# Connectors.net
KiCad netlist of a schematic drawn in Altium Designer
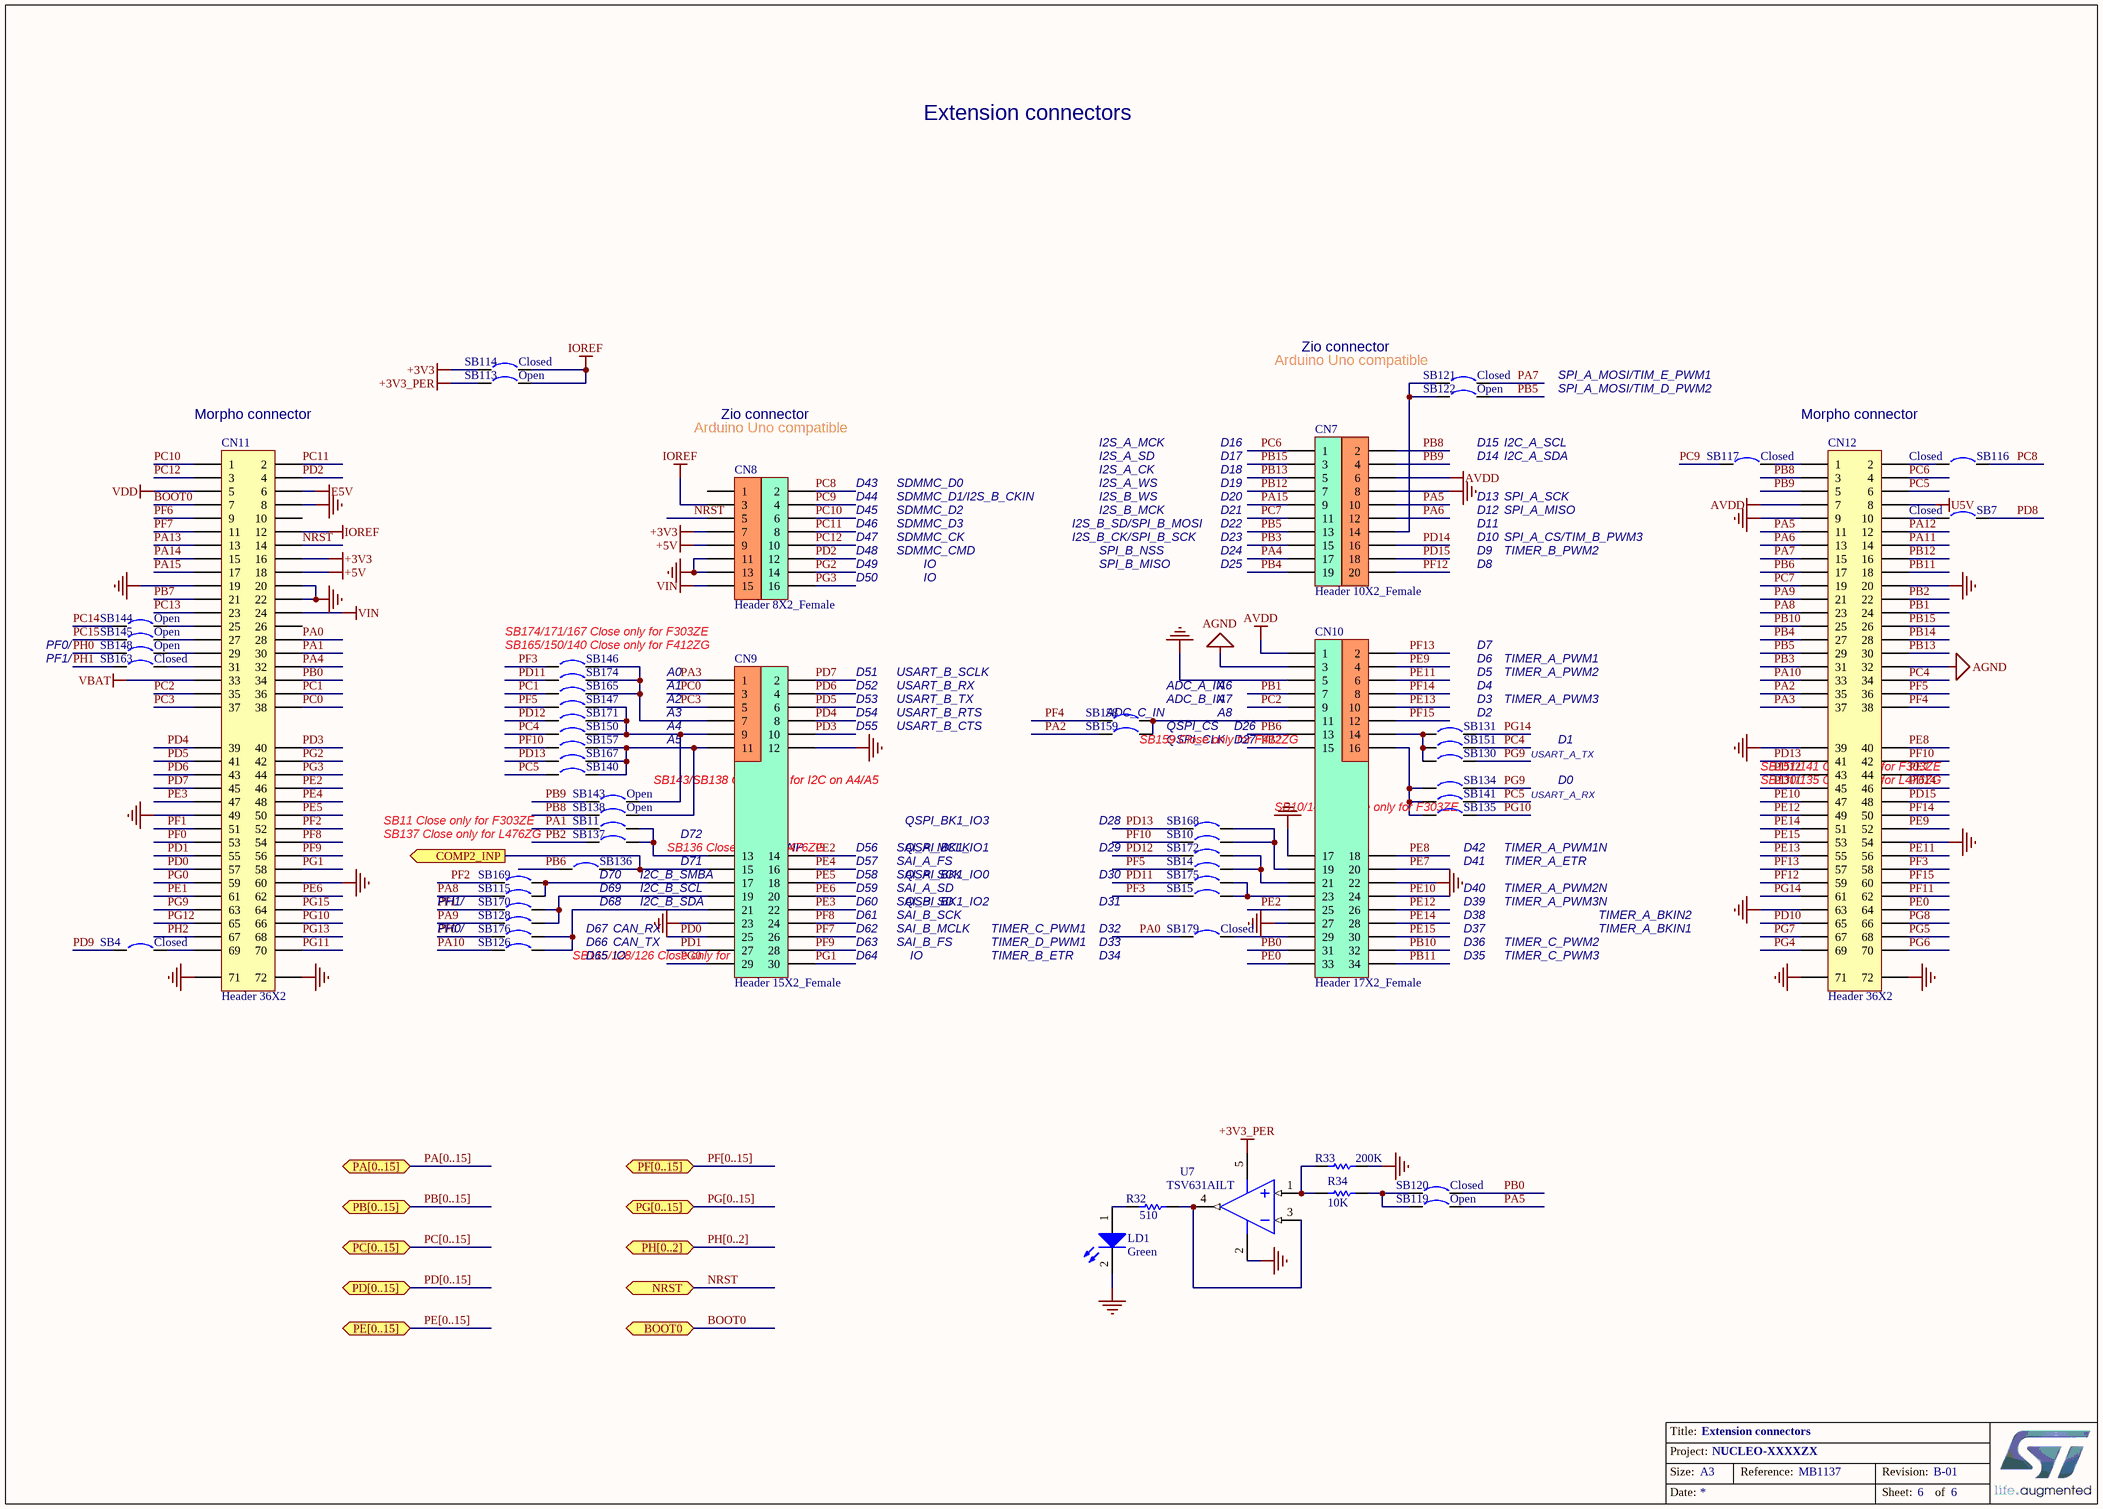
[diagram p0: Connectors.SchDoc]

(export (version "E")
  (design (tool "Eeschema 10.0.6"))
  (components
    (comp (ref "CN7")
      (value "Header 10X2_Female")
      (footprint "HDR_10x2_2R54_V_F")
      (description "Header, 10-Pin, Dual row,female")
      (fields (field (name "PUBLISHER") "Altium Limited"))
      (libsource (lib "MB1137") (part "Header 10X2_Female"))
    )
    (comp (ref "CN8")
      (value "Header 8X2_Female")
      (footprint "HDR_8x2_2R54_V_F")
      (description "Header, 8-Pin, Dual row,female")
      (fields (field (name "PUBLISHER") "Altium Limited"))
      (libsource (lib "MB1137") (part "Header 8X2_Female"))
    )
    (comp (ref "CN9")
      (value "Header 15X2_Female")
      (footprint "HDR_15x2_2R54_V_F")
      (description "Header, 15-Pin, Dual row,female")
      (fields (field (name "PUBLISHER") "Altium Limited"))
      (libsource (lib "MB1137") (part "Header 15X2_Female"))
    )
    (comp (ref "CN10")
      (value "Header 17X2_Female")
      (footprint "HDR_17x2_2R54_V_F")
      (description "Header, 17-Pin, Dual row,female")
      (fields (field (name "PUBLISHER") "Altium Limited"))
      (libsource (lib "MB1137") (part "Header 17X2_Female"))
    )
    (comp (ref "CN11")
      (value "Header 36X2")
      (footprint "HDR_2x36_2R54_V_M")
      (description "Header, 36-Pin, Dual row")
      (fields (field (name "PUBLISHER") "Altium Limited"))
      (libsource (lib "MB1137") (part "Header 36X2"))
    )
    (comp (ref "CN12")
      (value "Header 36X2")
      (footprint "HDR_2x36_2R54_V_M")
      (description "Header, 36-Pin, Dual row")
      (fields (field (name "PUBLISHER") "Altium Limited"))
      (libsource (lib "MB1137") (part "Header 36X2"))
    )
    (comp (ref "LD1")
      (value "Green")
      (footprint "0603D-G")
      (description "Typical RED, GREEN, YELLOW, AMBER GaAs LED")
      (fields (field (name "PUBLISHER") "Altium Limited"))
      (libsource (lib "Miscellaneous Devices") (part "LED2"))
    )
    (comp (ref "R32")
      (value "510")
      (footprint "0603R")
      (description "Resistor")
      (fields (field (name "PUBLISHER") "Altium Limited"))
      (libsource (lib "Miscellaneous Devices") (part "Res1"))
    )
    (comp (ref "R33")
      (value "200K")
      (footprint "0603R")
      (description "Resistor")
      (fields (field (name "PUBLISHER") "Altium Limited"))
      (libsource (lib "Miscellaneous Devices") (part "res1"))
    )
    (comp (ref "R34")
      (value "10K")
      (footprint "0603R")
      (description "Resistor")
      (fields (field (name "PUBLISHER") "Altium Limited"))
      (libsource (lib "Miscellaneous Devices") (part "res1"))
    )
    (comp (ref "SB4")
      (value "Closed")
      (footprint "SB_0603")
      (description "Circuit Breaker")
      (fields (field (name "PUBLISHER") "Altium Limited"))
      (libsource (lib "MB1167") (part "Circuit Breaker_close"))
    )
    (comp (ref "SB7")
      (value "Closed")
      (footprint "SB_0603")
      (description "Circuit Breaker")
      (fields (field (name "PUBLISHER") "Altium Limited"))
      (libsource (lib "MB1167") (part "Circuit Breaker_close"))
    )
    (comp (ref "SB10")
      (value "Circuit Breaker")
      (footprint "SB_0603")
      (fields (field (name "PUBLISHER") "Altium Limited"))
      (libsource (lib "") (part "Circuit Breaker_1"))
    )
    (comp (ref "SB11")
      (value "Circuit Breaker")
      (footprint "SB_0603")
      (fields (field (name "PUBLISHER") "Altium Limited"))
      (libsource (lib "MCD_TOOLS") (part "Circuit Breaker"))
    )
    (comp (ref "SB14")
      (value "Circuit Breaker")
      (footprint "SB_0603")
      (fields (field (name "PUBLISHER") "Altium Limited"))
      (libsource (lib "") (part "Circuit Breaker_1"))
    )
    (comp (ref "SB15")
      (value "Circuit Breaker")
      (footprint "SB_0603")
      (fields (field (name "PUBLISHER") "Altium Limited"))
      (libsource (lib "") (part "Circuit Breaker_1"))
    )
    (comp (ref "SB113")
      (value "Open")
      (footprint "SB_0603")
      (description "Circuit Breaker")
      (fields (field (name "PUBLISHER") "Altium Limited"))
      (libsource (lib "") (part "Circuit Breaker_1"))
    )
    (comp (ref "SB114")
      (value "Closed")
      (footprint "SB_0603")
      (description "Circuit Breaker")
      (fields (field (name "PUBLISHER") "Altium Limited"))
      (libsource (lib "MB1167") (part "Circuit Breaker_close"))
    )
    (comp (ref "SB115")
      (value "Circuit Breaker")
      (footprint "SB_0603")
      (fields (field (name "PUBLISHER") "Altium Limited"))
      (libsource (lib "MCD_TOOLS") (part "Circuit Breaker"))
    )
    (comp (ref "SB116")
      (value "Closed")
      (footprint "SB_0603")
      (description "Circuit Breaker")
      (fields (field (name "PUBLISHER") "Altium Limited"))
      (libsource (lib "") (part "Circuit Breaker_close_1"))
    )
    (comp (ref "SB117")
      (value "Closed")
      (footprint "SB_0603")
      (description "Circuit Breaker")
      (fields (field (name "PUBLISHER") "Altium Limited"))
      (libsource (lib "MB1167") (part "Circuit Breaker_close"))
    )
    (comp (ref "SB119")
      (value "Open")
      (footprint "SB_0603")
      (description "Circuit Breaker")
      (fields (field (name "PUBLISHER") "Altium Limited"))
      (libsource (lib "") (part "Circuit Breaker_1"))
    )
    (comp (ref "SB120")
      (value "Closed")
      (footprint "SB_0603")
      (description "Circuit Breaker")
      (fields (field (name "PUBLISHER") "Altium Limited"))
      (libsource (lib "") (part "Circuit Breaker_close_1"))
    )
    (comp (ref "SB121")
      (value "Closed")
      (footprint "SB_0603")
      (description "Circuit Breaker")
      (fields (field (name "PUBLISHER") "Altium Limited"))
      (libsource (lib "MB1167") (part "Circuit Breaker_close"))
    )
    (comp (ref "SB122")
      (value "Open")
      (footprint "SB_0603")
      (description "Circuit Breaker")
      (fields (field (name "PUBLISHER") "Altium Limited"))
      (libsource (lib "") (part "Circuit Breaker_1"))
    )
    (comp (ref "SB126")
      (value "Circuit Breaker")
      (footprint "SB_0603")
      (fields (field (name "PUBLISHER") "Altium Limited"))
      (libsource (lib "MCD_TOOLS") (part "Circuit Breaker"))
    )
    (comp (ref "SB128")
      (value "Circuit Breaker")
      (footprint "SB_0603")
      (fields (field (name "PUBLISHER") "Altium Limited"))
      (libsource (lib "MCD_TOOLS") (part "Circuit Breaker"))
    )
    (comp (ref "SB130")
      (value "Circuit Breaker")
      (footprint "SB_0603")
      (fields (field (name "PUBLISHER") "Altium Limited"))
      (libsource (lib "MCD_TOOLS") (part "Circuit Breaker"))
    )
    (comp (ref "SB131")
      (value "Circuit Breaker")
      (footprint "SB_0603")
      (fields (field (name "PUBLISHER") "Altium Limited"))
      (libsource (lib "MCD_TOOLS") (part "Circuit Breaker"))
    )
    (comp (ref "SB134")
      (value "Circuit Breaker")
      (footprint "SB_0603")
      (fields (field (name "PUBLISHER") "Altium Limited"))
      (libsource (lib "MCD_TOOLS") (part "Circuit Breaker"))
    )
    (comp (ref "SB135")
      (value "Circuit Breaker")
      (footprint "SB_0603")
      (fields (field (name "PUBLISHER") "Altium Limited"))
      (libsource (lib "MCD_TOOLS") (part "Circuit Breaker"))
    )
    (comp (ref "SB136")
      (value "Circuit Breaker")
      (footprint "SB_0603")
      (fields (field (name "PUBLISHER") "Altium Limited"))
      (libsource (lib "MCD_TOOLS") (part "Circuit Breaker"))
    )
    (comp (ref "SB137")
      (value "Circuit Breaker")
      (footprint "SB_0603")
      (fields (field (name "PUBLISHER") "Altium Limited"))
      (libsource (lib "MCD_TOOLS") (part "Circuit Breaker"))
    )
    (comp (ref "SB138")
      (value "Open")
      (footprint "SB_0603")
      (description "Circuit Breaker")
      (fields (field (name "PUBLISHER") "Altium Limited"))
      (libsource (lib "MB1167") (part "Circuit Breaker"))
    )
    (comp (ref "SB140")
      (value "Circuit Breaker")
      (footprint "SB_0603")
      (fields (field (name "PUBLISHER") "Altium Limited"))
      (libsource (lib "MCD_TOOLS") (part "Circuit Breaker"))
    )
    (comp (ref "SB141")
      (value "Circuit Breaker")
      (footprint "SB_0603")
      (fields (field (name "PUBLISHER") "Altium Limited"))
      (libsource (lib "MCD_TOOLS") (part "Circuit Breaker"))
    )
    (comp (ref "SB143")
      (value "Open")
      (footprint "SB_0603")
      (description "Circuit Breaker")
      (fields (field (name "PUBLISHER") "Altium Limited"))
      (libsource (lib "MB1167") (part "Circuit Breaker"))
    )
    (comp (ref "SB144")
      (value "Open")
      (footprint "SB_0603")
      (description "Circuit Breaker")
      (fields (field (name "PUBLISHER") "Altium Limited"))
      (libsource (lib "") (part "Circuit Breaker_1"))
    )
    (comp (ref "SB145")
      (value "Open")
      (footprint "SB_0603")
      (description "Circuit Breaker")
      (fields (field (name "PUBLISHER") "Altium Limited"))
      (libsource (lib "") (part "Circuit Breaker_1"))
    )
    (comp (ref "SB146")
      (value "Circuit Breaker")
      (footprint "SB_0603")
      (fields (field (name "PUBLISHER") "Altium Limited"))
      (libsource (lib "MCD_TOOLS") (part "Circuit Breaker"))
    )
    (comp (ref "SB147")
      (value "Circuit Breaker")
      (footprint "SB_0603")
      (fields (field (name "PUBLISHER") "Altium Limited"))
      (libsource (lib "MCD_TOOLS") (part "Circuit Breaker"))
    )
    (comp (ref "SB148")
      (value "Open")
      (footprint "SB_0603")
      (description "Circuit Breaker")
      (fields (field (name "PUBLISHER") "Altium Limited"))
      (libsource (lib "") (part "Circuit Breaker_1"))
    )
    (comp (ref "SB150")
      (value "Circuit Breaker")
      (footprint "SB_0603")
      (fields (field (name "PUBLISHER") "Altium Limited"))
      (libsource (lib "MCD_TOOLS") (part "Circuit Breaker"))
    )
    (comp (ref "SB151")
      (value "Circuit Breaker")
      (footprint "SB_0603")
      (fields (field (name "PUBLISHER") "Altium Limited"))
      (libsource (lib "MCD_TOOLS") (part "Circuit Breaker"))
    )
    (comp (ref "SB157")
      (value "Circuit Breaker")
      (footprint "SB_0603")
      (fields (field (name "PUBLISHER") "Altium Limited"))
      (libsource (lib "MCD_TOOLS") (part "Circuit Breaker"))
    )
    (comp (ref "SB158")
      (value "Circuit Breaker")
      (footprint "SB_0603")
      (fields (field (name "PUBLISHER") "Altium Limited"))
      (libsource (lib "") (part "Circuit Breaker_1"))
    )
    (comp (ref "SB159")
      (value "Circuit Breaker")
      (footprint "SB_0603")
      (fields (field (name "PUBLISHER") "Altium Limited"))
      (libsource (lib "") (part "Circuit Breaker_1"))
    )
    (comp (ref "SB163")
      (value "Closed")
      (footprint "SB_0603")
      (description "Circuit Breaker")
      (fields (field (name "PUBLISHER") "Altium Limited"))
      (libsource (lib "MB1167") (part "Circuit Breaker_close"))
    )
    (comp (ref "SB165")
      (value "Circuit Breaker")
      (footprint "SB_0603")
      (fields (field (name "PUBLISHER") "Altium Limited"))
      (libsource (lib "MCD_TOOLS") (part "Circuit Breaker"))
    )
    (comp (ref "SB167")
      (value "Circuit Breaker")
      (footprint "SB_0603")
      (fields (field (name "PUBLISHER") "Altium Limited"))
      (libsource (lib "MCD_TOOLS") (part "Circuit Breaker"))
    )
    (comp (ref "SB168")
      (value "Circuit Breaker")
      (footprint "SB_0603")
      (fields (field (name "PUBLISHER") "Altium Limited"))
      (libsource (lib "") (part "Circuit Breaker_1"))
    )
    (comp (ref "SB169")
      (value "Circuit Breaker")
      (footprint "SB_0603")
      (fields (field (name "PUBLISHER") "Altium Limited"))
      (libsource (lib "MCD_TOOLS") (part "Circuit Breaker"))
    )
    (comp (ref "SB170")
      (value "Circuit Breaker")
      (footprint "SB_0603")
      (fields (field (name "PUBLISHER") "Altium Limited"))
      (libsource (lib "MCD_TOOLS") (part "Circuit Breaker"))
    )
    (comp (ref "SB171")
      (value "Circuit Breaker")
      (footprint "SB_0603")
      (fields (field (name "PUBLISHER") "Altium Limited"))
      (libsource (lib "MCD_TOOLS") (part "Circuit Breaker"))
    )
    (comp (ref "SB172")
      (value "Circuit Breaker")
      (footprint "SB_0603")
      (fields (field (name "PUBLISHER") "Altium Limited"))
      (libsource (lib "") (part "Circuit Breaker_1"))
    )
    (comp (ref "SB174")
      (value "Circuit Breaker")
      (footprint "SB_0603")
      (fields (field (name "PUBLISHER") "Altium Limited"))
      (libsource (lib "MCD_TOOLS") (part "Circuit Breaker"))
    )
    (comp (ref "SB175")
      (value "Circuit Breaker")
      (footprint "SB_0603")
      (fields (field (name "PUBLISHER") "Altium Limited"))
      (libsource (lib "") (part "Circuit Breaker_1"))
    )
    (comp (ref "SB176")
      (value "Circuit Breaker")
      (footprint "SB_0603")
      (fields (field (name "PUBLISHER") "Altium Limited"))
      (libsource (lib "MCD_TOOLS") (part "Circuit Breaker"))
    )
    (comp (ref "SB179")
      (value "Closed")
      (footprint "SB_0603")
      (description "Circuit Breaker")
      (fields (field (name "PUBLISHER") "Altium Limited"))
      (libsource (lib "MB1167") (part "Circuit Breaker_close"))
    )
    (comp (ref "U7")
      (value "TSV631AILT")
      (footprint "SOT-23-5L")
      (libsource (lib "MB988") (part "TSV631AILT"))
    )
  )
  (nets
    (net (code "1") (name "+3V3") (class "Default")
      (node (ref "CN11") (pin "16") (pinfunction "16_16") (pintype "passive"))
      (node (ref "CN8") (pin "7") (pinfunction "7_7") (pintype "passive"))
      (node (ref "SB114") (pin "1") (pinfunction "1_1") (pintype "passive"))
    )
    (net (code "2") (name "+3V3_PER") (class "Default")
      (node (ref "SB113") (pin "1") (pinfunction "1_1") (pintype "passive"))
      (node (ref "U7") (pin "5") (pinfunction "VCC_5") (pintype "power_in"))
    )
    (net (code "3") (name "+5V") (class "Default")
      (node (ref "CN11") (pin "18") (pinfunction "18_18") (pintype "passive"))
      (node (ref "CN8") (pin "9") (pinfunction "9_9") (pintype "passive"))
    )
    (net (code "4") (name "/BOOT0") (class "Default")
      (node (ref "CN11") (pin "7") (pinfunction "7_7") (pintype "passive"))
    )
    (net (code "5") (name "/COMP2_INP") (class "Default")
      (node (ref "CN9") (pin "15") (pinfunction "15_15") (pintype "passive"))
      (node (ref "SB136") (pin "1") (pinfunction "1_1") (pintype "passive"))
    )
    (net (code "6") (name "/NRST") (class "Default")
      (node (ref "CN11") (pin "14") (pinfunction "14_14") (pintype "passive"))
      (node (ref "CN8") (pin "5") (pinfunction "5_5") (pintype "passive"))
    )
    (net (code "7") (name "/PA0") (class "Default")
      (node (ref "CN11") (pin "28") (pinfunction "28_28") (pintype "passive"))
      (node (ref "SB179") (pin "1") (pinfunction "1_1") (pintype "passive"))
    )
    (net (code "8") (name "/PA1") (class "Default")
      (node (ref "CN11") (pin "30") (pinfunction "30_30") (pintype "passive"))
      (node (ref "SB11") (pin "2") (pinfunction "2_2") (pintype "passive"))
    )
    (net (code "9") (name "/PA2") (class "Default")
      (node (ref "CN12") (pin "35") (pinfunction "35_35") (pintype "passive"))
      (node (ref "SB159") (pin "1") (pinfunction "1_1") (pintype "passive"))
    )
    (net (code "10") (name "/PA3") (class "Default")
      (node (ref "CN12") (pin "37") (pinfunction "37_37") (pintype "passive"))
      (node (ref "CN9") (pin "1") (pinfunction "1_1") (pintype "passive"))
    )
    (net (code "11") (name "/PA4") (class "Default")
      (node (ref "CN11") (pin "32") (pinfunction "32_32") (pintype "passive"))
      (node (ref "CN7") (pin "17") (pinfunction "17_17") (pintype "passive"))
    )
    (net (code "12") (name "/PA5") (class "Default")
      (node (ref "CN12") (pin "11") (pinfunction "11_11") (pintype "passive"))
      (node (ref "CN7") (pin "10") (pinfunction "10_10") (pintype "passive"))
      (node (ref "SB119") (pin "2") (pinfunction "2_2") (pintype "passive"))
    )
    (net (code "13") (name "/PA6") (class "Default")
      (node (ref "CN12") (pin "13") (pinfunction "13_13") (pintype "passive"))
      (node (ref "CN7") (pin "12") (pinfunction "12_12") (pintype "passive"))
    )
    (net (code "14") (name "/PA7") (class "Default")
      (node (ref "CN12") (pin "15") (pinfunction "15_15") (pintype "passive"))
      (node (ref "SB121") (pin "2") (pinfunction "2_2") (pintype "passive"))
    )
    (net (code "15") (name "/PA8") (class "Default")
      (node (ref "CN12") (pin "23") (pinfunction "23_23") (pintype "passive"))
      (node (ref "SB115") (pin "2") (pinfunction "2_2") (pintype "passive"))
    )
    (net (code "16") (name "/PA9") (class "Default")
      (node (ref "CN12") (pin "21") (pinfunction "21_21") (pintype "passive"))
      (node (ref "SB128") (pin "2") (pinfunction "2_2") (pintype "passive"))
    )
    (net (code "17") (name "/PA10") (class "Default")
      (node (ref "CN12") (pin "33") (pinfunction "33_33") (pintype "passive"))
      (node (ref "SB126") (pin "2") (pinfunction "2_2") (pintype "passive"))
    )
    (net (code "18") (name "/PA11") (class "Default")
      (node (ref "CN12") (pin "14") (pinfunction "14_14") (pintype "passive"))
    )
    (net (code "19") (name "/PA12") (class "Default")
      (node (ref "CN12") (pin "12") (pinfunction "12_12") (pintype "passive"))
    )
    (net (code "20") (name "/PA13") (class "Default")
      (node (ref "CN11") (pin "13") (pinfunction "13_13") (pintype "passive"))
    )
    (net (code "21") (name "/PA14") (class "Default")
      (node (ref "CN11") (pin "15") (pinfunction "15_15") (pintype "passive"))
    )
    (net (code "22") (name "/PA15") (class "Default")
      (node (ref "CN11") (pin "17") (pinfunction "17_17") (pintype "passive"))
      (node (ref "CN7") (pin "9") (pinfunction "9_9") (pintype "passive"))
    )
    (net (code "24") (name "/PB0") (class "Default")
      (node (ref "CN10") (pin "31") (pinfunction "31_31") (pintype "passive"))
      (node (ref "CN11") (pin "34") (pinfunction "34_34") (pintype "passive"))
      (node (ref "SB120") (pin "1") (pinfunction "1_1") (pintype "passive"))
    )
    (net (code "25") (name "/PB1") (class "Default")
      (node (ref "CN10") (pin "7") (pinfunction "7_7") (pintype "passive"))
      (node (ref "CN12") (pin "24") (pinfunction "24_24") (pintype "passive"))
    )
    (net (code "26") (name "/PB2") (class "Default")
      (node (ref "CN10") (pin "15") (pinfunction "15_15") (pintype "passive"))
      (node (ref "CN12") (pin "22") (pinfunction "22_22") (pintype "passive"))
      (node (ref "SB137") (pin "2") (pinfunction "2_2") (pintype "passive"))
    )
    (net (code "27") (name "/PB3") (class "Default")
      (node (ref "CN12") (pin "31") (pinfunction "31_31") (pintype "passive"))
      (node (ref "CN7") (pin "15") (pinfunction "15_15") (pintype "passive"))
    )
    (net (code "28") (name "/PB4") (class "Default")
      (node (ref "CN12") (pin "27") (pinfunction "27_27") (pintype "passive"))
      (node (ref "CN7") (pin "19") (pinfunction "19_19") (pintype "passive"))
    )
    (net (code "29") (name "/PB5") (class "Default")
      (node (ref "CN12") (pin "29") (pinfunction "29_29") (pintype "passive"))
      (node (ref "CN7") (pin "13") (pinfunction "13_13") (pintype "passive"))
      (node (ref "SB122") (pin "2") (pinfunction "2_2") (pintype "passive"))
    )
    (net (code "30") (name "/PB6") (class "Default")
      (node (ref "CN10") (pin "13") (pinfunction "13_13") (pintype "passive"))
      (node (ref "CN12") (pin "17") (pinfunction "17_17") (pintype "passive"))
      (node (ref "SB136") (pin "2") (pinfunction "2_2") (pintype "passive"))
    )
    (net (code "31") (name "/PB7") (class "Default")
      (node (ref "CN11") (pin "21") (pinfunction "21_21") (pintype "passive"))
    )
    (net (code "32") (name "/PB8") (class "Default")
      (node (ref "CN12") (pin "3") (pinfunction "3_3") (pintype "passive"))
      (node (ref "CN7") (pin "2") (pinfunction "2_2") (pintype "passive"))
      (node (ref "SB138") (pin "2") (pinfunction "2_2") (pintype "passive"))
    )
    (net (code "33") (name "/PB9") (class "Default")
      (node (ref "CN12") (pin "5") (pinfunction "5_5") (pintype "passive"))
      (node (ref "CN7") (pin "4") (pinfunction "4_4") (pintype "passive"))
      (node (ref "SB143") (pin "2") (pinfunction "2_2") (pintype "passive"))
    )
    (net (code "34") (name "/PB10") (class "Default")
      (node (ref "CN10") (pin "32") (pinfunction "32_32") (pintype "passive"))
      (node (ref "CN12") (pin "25") (pinfunction "25_25") (pintype "passive"))
    )
    (net (code "35") (name "/PB11") (class "Default")
      (node (ref "CN10") (pin "34") (pinfunction "34_34") (pintype "passive"))
      (node (ref "CN12") (pin "18") (pinfunction "18_18") (pintype "passive"))
    )
    (net (code "36") (name "/PB12") (class "Default")
      (node (ref "CN12") (pin "16") (pinfunction "16_16") (pintype "passive"))
      (node (ref "CN7") (pin "7") (pinfunction "7_7") (pintype "passive"))
    )
    (net (code "37") (name "/PB13") (class "Default")
      (node (ref "CN12") (pin "30") (pinfunction "30_30") (pintype "passive"))
      (node (ref "CN7") (pin "5") (pinfunction "5_5") (pintype "passive"))
    )
    (net (code "38") (name "/PB14") (class "Default")
      (node (ref "CN12") (pin "28") (pinfunction "28_28") (pintype "passive"))
    )
    (net (code "39") (name "/PB15") (class "Default")
      (node (ref "CN12") (pin "26") (pinfunction "26_26") (pintype "passive"))
      (node (ref "CN7") (pin "3") (pinfunction "3_3") (pintype "passive"))
    )
    (net (code "41") (name "/PC0") (class "Default")
      (node (ref "CN11") (pin "38") (pinfunction "38_38") (pintype "passive"))
      (node (ref "CN9") (pin "3") (pinfunction "3_3") (pintype "passive"))
    )
    (net (code "42") (name "/PC1") (class "Default")
      (node (ref "CN11") (pin "36") (pinfunction "36_36") (pintype "passive"))
      (node (ref "SB165") (pin "2") (pinfunction "2_2") (pintype "passive"))
    )
    (net (code "43") (name "/PC2") (class "Default")
      (node (ref "CN10") (pin "9") (pinfunction "9_9") (pintype "passive"))
      (node (ref "CN11") (pin "35") (pinfunction "35_35") (pintype "passive"))
    )
    (net (code "44") (name "/PC3") (class "Default")
      (node (ref "CN11") (pin "37") (pinfunction "37_37") (pintype "passive"))
      (node (ref "CN9") (pin "5") (pinfunction "5_5") (pintype "passive"))
    )
    (net (code "45") (name "/PC4") (class "Default")
      (node (ref "CN12") (pin "34") (pinfunction "34_34") (pintype "passive"))
      (node (ref "SB150") (pin "2") (pinfunction "2_2") (pintype "passive"))
      (node (ref "SB151") (pin "1") (pinfunction "1_1") (pintype "passive"))
    )
    (net (code "46") (name "/PC5") (class "Default")
      (node (ref "CN12") (pin "6") (pinfunction "6_6") (pintype "passive"))
      (node (ref "SB140") (pin "2") (pinfunction "2_2") (pintype "passive"))
      (node (ref "SB141") (pin "1") (pinfunction "1_1") (pintype "passive"))
    )
    (net (code "47") (name "/PC6") (class "Default")
      (node (ref "CN12") (pin "4") (pinfunction "4_4") (pintype "passive"))
      (node (ref "CN7") (pin "1") (pinfunction "1_1") (pintype "passive"))
    )
    (net (code "48") (name "/PC7") (class "Default")
      (node (ref "CN12") (pin "19") (pinfunction "19_19") (pintype "passive"))
      (node (ref "CN7") (pin "11") (pinfunction "11_11") (pintype "passive"))
    )
    (net (code "49") (name "/PC8") (class "Default")
      (node (ref "CN8") (pin "2") (pinfunction "2_2") (pintype "passive"))
      (node (ref "SB116") (pin "1") (pinfunction "1_1") (pintype "passive"))
    )
    (net (code "50") (name "/PC9") (class "Default")
      (node (ref "CN8") (pin "4") (pinfunction "4_4") (pintype "passive"))
      (node (ref "SB117") (pin "1") (pinfunction "1_1") (pintype "passive"))
    )
    (net (code "51") (name "/PC10") (class "Default")
      (node (ref "CN11") (pin "1") (pinfunction "1_1") (pintype "passive"))
      (node (ref "CN8") (pin "6") (pinfunction "6_6") (pintype "passive"))
    )
    (net (code "52") (name "/PC11") (class "Default")
      (node (ref "CN11") (pin "2") (pinfunction "2_2") (pintype "passive"))
      (node (ref "CN8") (pin "8") (pinfunction "8_8") (pintype "passive"))
    )
    (net (code "53") (name "/PC12") (class "Default")
      (node (ref "CN11") (pin "3") (pinfunction "3_3") (pintype "passive"))
      (node (ref "CN8") (pin "10") (pinfunction "10_10") (pintype "passive"))
    )
    (net (code "54") (name "/PC13") (class "Default")
      (node (ref "CN11") (pin "23") (pinfunction "23_23") (pintype "passive"))
    )
    (net (code "55") (name "/PC14") (class "Default")
      (node (ref "SB144") (pin "1") (pinfunction "1_1") (pintype "passive"))
    )
    (net (code "56") (name "/PC15") (class "Default")
      (node (ref "SB145") (pin "1") (pinfunction "1_1") (pintype "passive"))
    )
    (net (code "58") (name "/PD0") (class "Default")
      (node (ref "CN11") (pin "57") (pinfunction "57_57") (pintype "passive"))
      (node (ref "CN9") (pin "25") (pinfunction "25_25") (pintype "passive"))
    )
    (net (code "59") (name "/PD1") (class "Default")
      (node (ref "CN11") (pin "55") (pinfunction "55_55") (pintype "passive"))
      (node (ref "CN9") (pin "27") (pinfunction "27_27") (pintype "passive"))
    )
    (net (code "60") (name "/PD2") (class "Default")
      (node (ref "CN11") (pin "4") (pinfunction "4_4") (pintype "passive"))
      (node (ref "CN8") (pin "12") (pinfunction "12_12") (pintype "passive"))
    )
    (net (code "61") (name "/PD3") (class "Default")
      (node (ref "CN11") (pin "40") (pinfunction "40_40") (pintype "passive"))
      (node (ref "CN9") (pin "10") (pinfunction "10_10") (pintype "passive"))
    )
    (net (code "62") (name "/PD4") (class "Default")
      (node (ref "CN11") (pin "39") (pinfunction "39_39") (pintype "passive"))
      (node (ref "CN9") (pin "8") (pinfunction "8_8") (pintype "passive"))
    )
    (net (code "63") (name "/PD5") (class "Default")
      (node (ref "CN11") (pin "41") (pinfunction "41_41") (pintype "passive"))
      (node (ref "CN9") (pin "6") (pinfunction "6_6") (pintype "passive"))
    )
    (net (code "64") (name "/PD6") (class "Default")
      (node (ref "CN11") (pin "43") (pinfunction "43_43") (pintype "passive"))
      (node (ref "CN9") (pin "4") (pinfunction "4_4") (pintype "passive"))
    )
    (net (code "65") (name "/PD7") (class "Default")
      (node (ref "CN11") (pin "45") (pinfunction "45_45") (pintype "passive"))
      (node (ref "CN9") (pin "2") (pinfunction "2_2") (pintype "passive"))
    )
    (net (code "66") (name "/PD8") (class "Default")
      (node (ref "SB7") (pin "2") (pinfunction "2_2") (pintype "passive"))
    )
    (net (code "67") (name "/PD9") (class "Default")
      (node (ref "SB4") (pin "1") (pinfunction "1_1") (pintype "passive"))
    )
    (net (code "68") (name "/PD10") (class "Default")
      (node (ref "CN12") (pin "65") (pinfunction "65_65") (pintype "passive"))
    )
    (net (code "69") (name "/PD11") (class "Default")
      (node (ref "CN12") (pin "45") (pinfunction "45_45") (pintype "passive"))
      (node (ref "SB174") (pin "2") (pinfunction "2_2") (pintype "passive"))
      (node (ref "SB175") (pin "1") (pinfunction "1_1") (pintype "passive"))
    )
    (net (code "70") (name "/PD12") (class "Default")
      (node (ref "CN12") (pin "43") (pinfunction "43_43") (pintype "passive"))
      (node (ref "SB171") (pin "2") (pinfunction "2_2") (pintype "passive"))
      (node (ref "SB172") (pin "1") (pinfunction "1_1") (pintype "passive"))
    )
    (net (code "71") (name "/PD13") (class "Default")
      (node (ref "CN12") (pin "41") (pinfunction "41_41") (pintype "passive"))
      (node (ref "SB167") (pin "2") (pinfunction "2_2") (pintype "passive"))
      (node (ref "SB168") (pin "1") (pinfunction "1_1") (pintype "passive"))
    )
    (net (code "72") (name "/PD14") (class "Default")
      (node (ref "CN12") (pin "46") (pinfunction "46_46") (pintype "passive"))
      (node (ref "CN7") (pin "16") (pinfunction "16_16") (pintype "passive"))
    )
    (net (code "73") (name "/PD15") (class "Default")
      (node (ref "CN12") (pin "48") (pinfunction "48_48") (pintype "passive"))
      (node (ref "CN7") (pin "18") (pinfunction "18_18") (pintype "passive"))
    )
    (net (code "75") (name "/PE0") (class "Default")
      (node (ref "CN10") (pin "33") (pinfunction "33_33") (pintype "passive"))
      (node (ref "CN12") (pin "64") (pinfunction "64_64") (pintype "passive"))
    )
    (net (code "76") (name "/PE1") (class "Default")
      (node (ref "CN11") (pin "61") (pinfunction "61_61") (pintype "passive"))
    )
    (net (code "77") (name "/PE2") (class "Default")
      (node (ref "CN10") (pin "25") (pinfunction "25_25") (pintype "passive"))
      (node (ref "CN11") (pin "46") (pinfunction "46_46") (pintype "passive"))
      (node (ref "CN9") (pin "14") (pinfunction "14_14") (pintype "passive"))
    )
    (net (code "78") (name "/PE3") (class "Default")
      (node (ref "CN11") (pin "47") (pinfunction "47_47") (pintype "passive"))
      (node (ref "CN9") (pin "22") (pinfunction "22_22") (pintype "passive"))
    )
    (net (code "79") (name "/PE4") (class "Default")
      (node (ref "CN11") (pin "48") (pinfunction "48_48") (pintype "passive"))
      (node (ref "CN9") (pin "16") (pinfunction "16_16") (pintype "passive"))
    )
    (net (code "80") (name "/PE5") (class "Default")
      (node (ref "CN11") (pin "50") (pinfunction "50_50") (pintype "passive"))
      (node (ref "CN9") (pin "18") (pinfunction "18_18") (pintype "passive"))
    )
    (net (code "81") (name "/PE6") (class "Default")
      (node (ref "CN11") (pin "62") (pinfunction "62_62") (pintype "passive"))
      (node (ref "CN9") (pin "20") (pinfunction "20_20") (pintype "passive"))
    )
    (net (code "82") (name "/PE7") (class "Default")
      (node (ref "CN10") (pin "20") (pinfunction "20_20") (pintype "passive"))
      (node (ref "CN12") (pin "44") (pinfunction "44_44") (pintype "passive"))
    )
    (net (code "83") (name "/PE8") (class "Default")
      (node (ref "CN10") (pin "18") (pinfunction "18_18") (pintype "passive"))
      (node (ref "CN12") (pin "40") (pinfunction "40_40") (pintype "passive"))
    )
    (net (code "84") (name "/PE9") (class "Default")
      (node (ref "CN10") (pin "4") (pinfunction "4_4") (pintype "passive"))
      (node (ref "CN12") (pin "52") (pinfunction "52_52") (pintype "passive"))
    )
    (net (code "85") (name "/PE10") (class "Default")
      (node (ref "CN10") (pin "24") (pinfunction "24_24") (pintype "passive"))
      (node (ref "CN12") (pin "47") (pinfunction "47_47") (pintype "passive"))
    )
    (net (code "86") (name "/PE11") (class "Default")
      (node (ref "CN10") (pin "6") (pinfunction "6_6") (pintype "passive"))
      (node (ref "CN12") (pin "56") (pinfunction "56_56") (pintype "passive"))
    )
    (net (code "87") (name "/PE12") (class "Default")
      (node (ref "CN10") (pin "26") (pinfunction "26_26") (pintype "passive"))
      (node (ref "CN12") (pin "49") (pinfunction "49_49") (pintype "passive"))
    )
    (net (code "88") (name "/PE13") (class "Default")
      (node (ref "CN10") (pin "10") (pinfunction "10_10") (pintype "passive"))
      (node (ref "CN12") (pin "55") (pinfunction "55_55") (pintype "passive"))
    )
    (net (code "89") (name "/PE14") (class "Default")
      (node (ref "CN10") (pin "28") (pinfunction "28_28") (pintype "passive"))
      (node (ref "CN12") (pin "51") (pinfunction "51_51") (pintype "passive"))
    )
    (net (code "90") (name "/PE15") (class "Default")
      (node (ref "CN10") (pin "30") (pinfunction "30_30") (pintype "passive"))
      (node (ref "CN12") (pin "53") (pinfunction "53_53") (pintype "passive"))
    )
    (net (code "92") (name "/PF0") (class "Default")
      (node (ref "CN11") (pin "53") (pinfunction "53_53") (pintype "passive"))
      (node (ref "SB176") (pin "2") (pinfunction "2_2") (pintype "passive"))
    )
    (net (code "93") (name "/PF1") (class "Default")
      (node (ref "CN11") (pin "51") (pinfunction "51_51") (pintype "passive"))
      (node (ref "SB170") (pin "2") (pinfunction "2_2") (pintype "passive"))
    )
    (net (code "94") (name "/PF2") (class "Default")
      (node (ref "CN11") (pin "52") (pinfunction "52_52") (pintype "passive"))
      (node (ref "SB169") (pin "2") (pinfunction "2_2") (pintype "passive"))
    )
    (net (code "95") (name "/PF3") (class "Default")
      (node (ref "CN12") (pin "58") (pinfunction "58_58") (pintype "passive"))
      (node (ref "SB146") (pin "2") (pinfunction "2_2") (pintype "passive"))
      (node (ref "SB15") (pin "1") (pinfunction "1_1") (pintype "passive"))
    )
    (net (code "96") (name "/PF4") (class "Default")
      (node (ref "CN12") (pin "38") (pinfunction "38_38") (pintype "passive"))
      (node (ref "SB158") (pin "1") (pinfunction "1_1") (pintype "passive"))
    )
    (net (code "97") (name "/PF5") (class "Default")
      (node (ref "CN12") (pin "36") (pinfunction "36_36") (pintype "passive"))
      (node (ref "SB14") (pin "1") (pinfunction "1_1") (pintype "passive"))
      (node (ref "SB147") (pin "2") (pinfunction "2_2") (pintype "passive"))
    )
    (net (code "98") (name "/PF6") (class "Default")
      (node (ref "CN11") (pin "9") (pinfunction "9_9") (pintype "passive"))
    )
    (net (code "99") (name "/PF7") (class "Default")
      (node (ref "CN11") (pin "11") (pinfunction "11_11") (pintype "passive"))
      (node (ref "CN9") (pin "26") (pinfunction "26_26") (pintype "passive"))
    )
    (net (code "100") (name "/PF8") (class "Default")
      (node (ref "CN11") (pin "54") (pinfunction "54_54") (pintype "passive"))
      (node (ref "CN9") (pin "24") (pinfunction "24_24") (pintype "passive"))
    )
    (net (code "101") (name "/PF9") (class "Default")
      (node (ref "CN11") (pin "56") (pinfunction "56_56") (pintype "passive"))
      (node (ref "CN9") (pin "28") (pinfunction "28_28") (pintype "passive"))
    )
    (net (code "102") (name "/PF10") (class "Default")
      (node (ref "CN12") (pin "42") (pinfunction "42_42") (pintype "passive"))
      (node (ref "SB10") (pin "1") (pinfunction "1_1") (pintype "passive"))
      (node (ref "SB157") (pin "2") (pinfunction "2_2") (pintype "passive"))
    )
    (net (code "103") (name "/PF11") (class "Default")
      (node (ref "CN12") (pin "62") (pinfunction "62_62") (pintype "passive"))
    )
    (net (code "104") (name "/PF12") (class "Default")
      (node (ref "CN12") (pin "59") (pinfunction "59_59") (pintype "passive"))
      (node (ref "CN7") (pin "20") (pinfunction "20_20") (pintype "passive"))
    )
    (net (code "105") (name "/PF13") (class "Default")
      (node (ref "CN10") (pin "2") (pinfunction "2_2") (pintype "passive"))
      (node (ref "CN12") (pin "57") (pinfunction "57_57") (pintype "passive"))
    )
    (net (code "106") (name "/PF14") (class "Default")
      (node (ref "CN10") (pin "8") (pinfunction "8_8") (pintype "passive"))
      (node (ref "CN12") (pin "50") (pinfunction "50_50") (pintype "passive"))
    )
    (net (code "107") (name "/PF15") (class "Default")
      (node (ref "CN10") (pin "12") (pinfunction "12_12") (pintype "passive"))
      (node (ref "CN12") (pin "60") (pinfunction "60_60") (pintype "passive"))
    )
    (net (code "109") (name "/PG0") (class "Default")
      (node (ref "CN11") (pin "59") (pinfunction "59_59") (pintype "passive"))
      (node (ref "CN9") (pin "29") (pinfunction "29_29") (pintype "passive"))
    )
    (net (code "110") (name "/PG1") (class "Default")
      (node (ref "CN11") (pin "58") (pinfunction "58_58") (pintype "passive"))
      (node (ref "CN9") (pin "30") (pinfunction "30_30") (pintype "passive"))
    )
    (net (code "111") (name "/PG2") (class "Default")
      (node (ref "CN11") (pin "42") (pinfunction "42_42") (pintype "passive"))
      (node (ref "CN8") (pin "14") (pinfunction "14_14") (pintype "passive"))
    )
    (net (code "112") (name "/PG3") (class "Default")
      (node (ref "CN11") (pin "44") (pinfunction "44_44") (pintype "passive"))
      (node (ref "CN8") (pin "16") (pinfunction "16_16") (pintype "passive"))
    )
    (net (code "113") (name "/PG4") (class "Default")
      (node (ref "CN12") (pin "69") (pinfunction "69_69") (pintype "passive"))
    )
    (net (code "114") (name "/PG5") (class "Default")
      (node (ref "CN12") (pin "68") (pinfunction "68_68") (pintype "passive"))
    )
    (net (code "115") (name "/PG6") (class "Default")
      (node (ref "CN12") (pin "70") (pinfunction "70_70") (pintype "passive"))
    )
    (net (code "116") (name "/PG7") (class "Default")
      (node (ref "CN12") (pin "67") (pinfunction "67_67") (pintype "passive"))
    )
    (net (code "117") (name "/PG8") (class "Default")
      (node (ref "CN12") (pin "66") (pinfunction "66_66") (pintype "passive"))
    )
    (net (code "118") (name "/PG9") (class "Default")
      (node (ref "CN11") (pin "63") (pinfunction "63_63") (pintype "passive"))
      (node (ref "SB130") (pin "1") (pinfunction "1_1") (pintype "passive"))
      (node (ref "SB134") (pin "1") (pinfunction "1_1") (pintype "passive"))
    )
    (net (code "119") (name "/PG10") (class "Default")
      (node (ref "CN11") (pin "66") (pinfunction "66_66") (pintype "passive"))
      (node (ref "SB135") (pin "1") (pinfunction "1_1") (pintype "passive"))
    )
    (net (code "120") (name "/PG11") (class "Default")
      (node (ref "CN11") (pin "70") (pinfunction "70_70") (pintype "passive"))
    )
    (net (code "121") (name "/PG12") (class "Default")
      (node (ref "CN11") (pin "65") (pinfunction "65_65") (pintype "passive"))
    )
    (net (code "122") (name "/PG13") (class "Default")
      (node (ref "CN11") (pin "68") (pinfunction "68_68") (pintype "passive"))
    )
    (net (code "123") (name "/PG14") (class "Default")
      (node (ref "CN12") (pin "61") (pinfunction "61_61") (pintype "passive"))
      (node (ref "SB131") (pin "1") (pinfunction "1_1") (pintype "passive"))
    )
    (net (code "124") (name "/PG15") (class "Default")
      (node (ref "CN11") (pin "64") (pinfunction "64_64") (pintype "passive"))
    )
    (net (code "126") (name "/PH0") (class "Default")
      (node (ref "SB148") (pin "1") (pinfunction "1_1") (pintype "passive"))
    )
    (net (code "127") (name "/PH1") (class "Default")
      (node (ref "SB163") (pin "1") (pinfunction "1_1") (pintype "passive"))
    )
    (net (code "128") (name "/PH2") (class "Default")
      (node (ref "CN11") (pin "67") (pinfunction "67_67") (pintype "passive"))
    )
    (net (code "130") (name "AGND") (class "Default")
      (node (ref "CN10") (pin "3") (pinfunction "3_3") (pintype "passive"))
      (node (ref "CN12") (pin "32") (pinfunction "32_32") (pintype "passive"))
    )
    (net (code "131") (name "AVDD") (class "Default")
      (node (ref "CN10") (pin "1") (pinfunction "1_1") (pintype "passive"))
      (node (ref "CN12") (pin "7") (pinfunction "7_7") (pintype "passive"))
      (node (ref "CN7") (pin "6") (pinfunction "6_6") (pintype "passive"))
    )
    (net (code "132") (name "E5V") (class "Default")
      (node (ref "CN11") (pin "6") (pinfunction "6_6") (pintype "passive"))
    )
    (net (code "133") (name "GND") (class "Default")
      (node (ref "CN10") (pin "17") (pinfunction "17_17") (pintype "passive"))
      (node (ref "CN10") (pin "22") (pinfunction "22_22") (pintype "passive"))
      (node (ref "CN10") (pin "27") (pinfunction "27_27") (pintype "passive"))
      (node (ref "CN10") (pin "5") (pinfunction "5_5") (pintype "passive"))
      (node (ref "CN11") (pin "19") (pinfunction "19_19") (pintype "passive"))
      (node (ref "CN11") (pin "20") (pinfunction "20_20") (pintype "passive"))
      (node (ref "CN11") (pin "22") (pinfunction "22_22") (pintype "passive"))
      (node (ref "CN11") (pin "49") (pinfunction "49_49") (pintype "passive"))
      (node (ref "CN11") (pin "60") (pinfunction "60_60") (pintype "passive"))
      (node (ref "CN11") (pin "71") (pinfunction "71_71") (pintype "passive"))
      (node (ref "CN11") (pin "72") (pinfunction "72_72") (pintype "passive"))
      (node (ref "CN11") (pin "8") (pinfunction "8_8") (pintype "passive"))
      (node (ref "CN12") (pin "20") (pinfunction "20_20") (pintype "passive"))
      (node (ref "CN12") (pin "39") (pinfunction "39_39") (pintype "passive"))
      (node (ref "CN12") (pin "54") (pinfunction "54_54") (pintype "passive"))
      (node (ref "CN12") (pin "63") (pinfunction "63_63") (pintype "passive"))
      (node (ref "CN12") (pin "71") (pinfunction "71_71") (pintype "passive"))
      (node (ref "CN12") (pin "72") (pinfunction "72_72") (pintype "passive"))
      (node (ref "CN12") (pin "9") (pinfunction "9_9") (pintype "passive"))
      (node (ref "CN7") (pin "8") (pinfunction "8_8") (pintype "passive"))
      (node (ref "CN8") (pin "11") (pinfunction "11_11") (pintype "passive"))
      (node (ref "CN8") (pin "13") (pinfunction "13_13") (pintype "passive"))
      (node (ref "CN9") (pin "12") (pinfunction "12_12") (pintype "passive"))
      (node (ref "CN9") (pin "23") (pinfunction "23_23") (pintype "passive"))
      (node (ref "LD1") (pin "2") (pinfunction "K_2") (pintype "passive"))
      (node (ref "R33") (pin "2") (pinfunction "2_2") (pintype "passive"))
      (node (ref "U7") (pin "2") (pinfunction "VDD_2") (pintype "power_in"))
    )
    (net (code "134") (name "IOREF") (class "Default")
      (node (ref "CN11") (pin "12") (pinfunction "12_12") (pintype "passive"))
      (node (ref "CN8") (pin "3") (pinfunction "3_3") (pintype "passive"))
      (node (ref "SB113") (pin "2") (pinfunction "2_2") (pintype "passive"))
      (node (ref "SB114") (pin "2") (pinfunction "2_2") (pintype "passive"))
    )
    (net (code "135") (name "Net-(CN7-Pad14)") (class "Default")
      (node (ref "CN7") (pin "14") (pinfunction "14_14") (pintype "passive"))
      (node (ref "SB121") (pin "1") (pinfunction "1_1") (pintype "passive"))
      (node (ref "SB122") (pin "1") (pinfunction "1_1") (pintype "passive"))
    )
    (net (code "136") (name "Net-(CN9-Pad7)") (class "Default")
      (node (ref "CN9") (pin "7") (pinfunction "7_7") (pintype "passive"))
      (node (ref "SB146") (pin "1") (pinfunction "1_1") (pintype "passive"))
      (node (ref "SB165") (pin "1") (pinfunction "1_1") (pintype "passive"))
      (node (ref "SB174") (pin "1") (pinfunction "1_1") (pintype "passive"))
    )
    (net (code "137") (name "Net-(CN9-Pad9)") (class "Default")
      (node (ref "CN9") (pin "9") (pinfunction "9_9") (pintype "passive"))
      (node (ref "SB143") (pin "1") (pinfunction "1_1") (pintype "passive"))
      (node (ref "SB147") (pin "1") (pinfunction "1_1") (pintype "passive"))
      (node (ref "SB150") (pin "1") (pinfunction "1_1") (pintype "passive"))
      (node (ref "SB171") (pin "1") (pinfunction "1_1") (pintype "passive"))
    )
    (net (code "138") (name "Net-(CN9-Pad11)") (class "Default")
      (node (ref "CN9") (pin "11") (pinfunction "11_11") (pintype "passive"))
      (node (ref "SB138") (pin "1") (pinfunction "1_1") (pintype "passive"))
      (node (ref "SB140") (pin "1") (pinfunction "1_1") (pintype "passive"))
      (node (ref "SB157") (pin "1") (pinfunction "1_1") (pintype "passive"))
      (node (ref "SB167") (pin "1") (pinfunction "1_1") (pintype "passive"))
    )
    (net (code "139") (name "Net-(CN9-Pad13)") (class "Default")
      (node (ref "CN9") (pin "13") (pinfunction "13_13") (pintype "passive"))
      (node (ref "SB11") (pin "1") (pinfunction "1_1") (pintype "passive"))
      (node (ref "SB137") (pin "1") (pinfunction "1_1") (pintype "passive"))
    )
    (net (code "140") (name "Net-(CN9-Pad17)") (class "Default")
      (node (ref "CN9") (pin "17") (pinfunction "17_17") (pintype "passive"))
      (node (ref "SB115") (pin "1") (pinfunction "1_1") (pintype "passive"))
      (node (ref "SB169") (pin "1") (pinfunction "1_1") (pintype "passive"))
    )
    (net (code "141") (name "Net-(CN9-Pad19)") (class "Default")
      (node (ref "CN9") (pin "19") (pinfunction "19_19") (pintype "passive"))
      (node (ref "SB128") (pin "1") (pinfunction "1_1") (pintype "passive"))
      (node (ref "SB170") (pin "1") (pinfunction "1_1") (pintype "passive"))
    )
    (net (code "142") (name "Net-(CN9-Pad21)") (class "Default")
      (node (ref "CN9") (pin "21") (pinfunction "21_21") (pintype "passive"))
      (node (ref "SB126") (pin "1") (pinfunction "1_1") (pintype "passive"))
      (node (ref "SB176") (pin "1") (pinfunction "1_1") (pintype "passive"))
    )
    (net (code "143") (name "Net-(CN10-Pad11)") (class "Default")
      (node (ref "CN10") (pin "11") (pinfunction "11_11") (pintype "passive"))
      (node (ref "SB158") (pin "2") (pinfunction "2_2") (pintype "passive"))
      (node (ref "SB159") (pin "2") (pinfunction "2_2") (pintype "passive"))
    )
    (net (code "144") (name "Net-(CN10-Pad14)") (class "Default")
      (node (ref "CN10") (pin "14") (pinfunction "14_14") (pintype "passive"))
      (node (ref "SB130") (pin "2") (pinfunction "2_2") (pintype "passive"))
      (node (ref "SB131") (pin "2") (pinfunction "2_2") (pintype "passive"))
      (node (ref "SB151") (pin "2") (pinfunction "2_2") (pintype "passive"))
    )
    (net (code "145") (name "Net-(CN10-Pad16)") (class "Default")
      (node (ref "CN10") (pin "16") (pinfunction "16_16") (pintype "passive"))
      (node (ref "SB134") (pin "2") (pinfunction "2_2") (pintype "passive"))
      (node (ref "SB135") (pin "2") (pinfunction "2_2") (pintype "passive"))
      (node (ref "SB141") (pin "2") (pinfunction "2_2") (pintype "passive"))
    )
    (net (code "146") (name "Net-(CN10-Pad19)") (class "Default")
      (node (ref "CN10") (pin "19") (pinfunction "19_19") (pintype "passive"))
      (node (ref "SB10") (pin "2") (pinfunction "2_2") (pintype "passive"))
      (node (ref "SB168") (pin "2") (pinfunction "2_2") (pintype "passive"))
    )
    (net (code "147") (name "Net-(CN10-Pad21)") (class "Default")
      (node (ref "CN10") (pin "21") (pinfunction "21_21") (pintype "passive"))
      (node (ref "SB14") (pin "2") (pinfunction "2_2") (pintype "passive"))
      (node (ref "SB172") (pin "2") (pinfunction "2_2") (pintype "passive"))
    )
    (net (code "148") (name "Net-(CN10-Pad23)") (class "Default")
      (node (ref "CN10") (pin "23") (pinfunction "23_23") (pintype "passive"))
      (node (ref "SB15") (pin "2") (pinfunction "2_2") (pintype "passive"))
      (node (ref "SB175") (pin "2") (pinfunction "2_2") (pintype "passive"))
    )
    (net (code "149") (name "Net-(CN10-Pad29)") (class "Default")
      (node (ref "CN10") (pin "29") (pinfunction "29_29") (pintype "passive"))
      (node (ref "SB179") (pin "2") (pinfunction "2_2") (pintype "passive"))
    )
    (net (code "150") (name "Net-(CN11-Pad25)") (class "Default")
      (node (ref "CN11") (pin "25") (pinfunction "25_25") (pintype "passive"))
      (node (ref "SB144") (pin "2") (pinfunction "2_2") (pintype "passive"))
    )
    (net (code "151") (name "Net-(CN11-Pad27)") (class "Default")
      (node (ref "CN11") (pin "27") (pinfunction "27_27") (pintype "passive"))
      (node (ref "SB145") (pin "2") (pinfunction "2_2") (pintype "passive"))
    )
    (net (code "152") (name "Net-(CN11-Pad29)") (class "Default")
      (node (ref "CN11") (pin "29") (pinfunction "29_29") (pintype "passive"))
      (node (ref "SB148") (pin "2") (pinfunction "2_2") (pintype "passive"))
    )
    (net (code "153") (name "Net-(CN11-Pad31)") (class "Default")
      (node (ref "CN11") (pin "31") (pinfunction "31_31") (pintype "passive"))
      (node (ref "SB163") (pin "2") (pinfunction "2_2") (pintype "passive"))
    )
    (net (code "154") (name "Net-(CN11-Pad69)") (class "Default")
      (node (ref "CN11") (pin "69") (pinfunction "69_69") (pintype "passive"))
      (node (ref "SB4") (pin "2") (pinfunction "2_2") (pintype "passive"))
    )
    (net (code "155") (name "Net-(CN12-Pad1)") (class "Default")
      (node (ref "CN12") (pin "1") (pinfunction "1_1") (pintype "passive"))
      (node (ref "SB117") (pin "2") (pinfunction "2_2") (pintype "passive"))
    )
    (net (code "156") (name "Net-(CN12-Pad2)") (class "Default")
      (node (ref "CN12") (pin "2") (pinfunction "2_2") (pintype "passive"))
      (node (ref "SB116") (pin "2") (pinfunction "2_2") (pintype "passive"))
    )
    (net (code "157") (name "Net-(CN12-Pad10)") (class "Default")
      (node (ref "CN12") (pin "10") (pinfunction "10_10") (pintype "passive"))
      (node (ref "SB7") (pin "1") (pinfunction "1_1") (pintype "passive"))
    )
    (net (code "158") (name "Net-(LD1-A)") (class "Default")
      (node (ref "LD1") (pin "1") (pinfunction "A_1") (pintype "passive"))
      (node (ref "R32") (pin "2") (pinfunction "2_2") (pintype "passive"))
    )
    (net (code "159") (name "Net-(R34-Pad2)") (class "Default")
      (node (ref "R34") (pin "2") (pinfunction "2_2") (pintype "passive"))
      (node (ref "SB119") (pin "1") (pinfunction "1_1") (pintype "passive"))
      (node (ref "SB120") (pin "2") (pinfunction "2_2") (pintype "passive"))
    )
    (net (code "160") (name "Net-(U7-IN+)") (class "Default")
      (node (ref "R33") (pin "1") (pinfunction "1_1") (pintype "passive"))
      (node (ref "R34") (pin "1") (pinfunction "1_1") (pintype "passive"))
      (node (ref "U7") (pin "1") (pinfunction "IN+_1") (pintype "input"))
    )
    (net (code "161") (name "Net-(U7-IN-)") (class "Default")
      (node (ref "R32") (pin "1") (pinfunction "1_1") (pintype "passive"))
      (node (ref "U7") (pin "3") (pinfunction "IN-_3") (pintype "input"))
      (node (ref "U7") (pin "4") (pinfunction "OUT_4") (pintype "output"))
    )
    (net (code "162") (name "U5V") (class "Default")
      (node (ref "CN12") (pin "8") (pinfunction "8_8") (pintype "passive"))
    )
    (net (code "163") (name "VBAT") (class "Default")
      (node (ref "CN11") (pin "33") (pinfunction "33_33") (pintype "passive"))
    )
    (net (code "164") (name "VDD") (class "Default")
      (node (ref "CN11") (pin "5") (pinfunction "5_5") (pintype "passive"))
    )
    (net (code "165") (name "VIN") (class "Default")
      (node (ref "CN11") (pin "24") (pinfunction "24_24") (pintype "passive"))
      (node (ref "CN8") (pin "15") (pinfunction "15_15") (pintype "passive"))
    )
    (net (code "166") (name "unconnected-(CN8-Pad1)") (class "Default")
      (node (ref "CN8") (pin "1") (pinfunction "1_1") (pintype "passive"))
    )
    (net (code "167") (name "unconnected-(CN11-Pad10)") (class "Default")
      (node (ref "CN11") (pin "10") (pinfunction "10_10") (pintype "passive"))
    )
    (net (code "168") (name "unconnected-(CN11-Pad26)") (class "Default")
      (node (ref "CN11") (pin "26") (pinfunction "26_26") (pintype "passive"))
    )
  )
)
